# oscillators.net
KiCad netlist of a schematic drawn in EAGLE
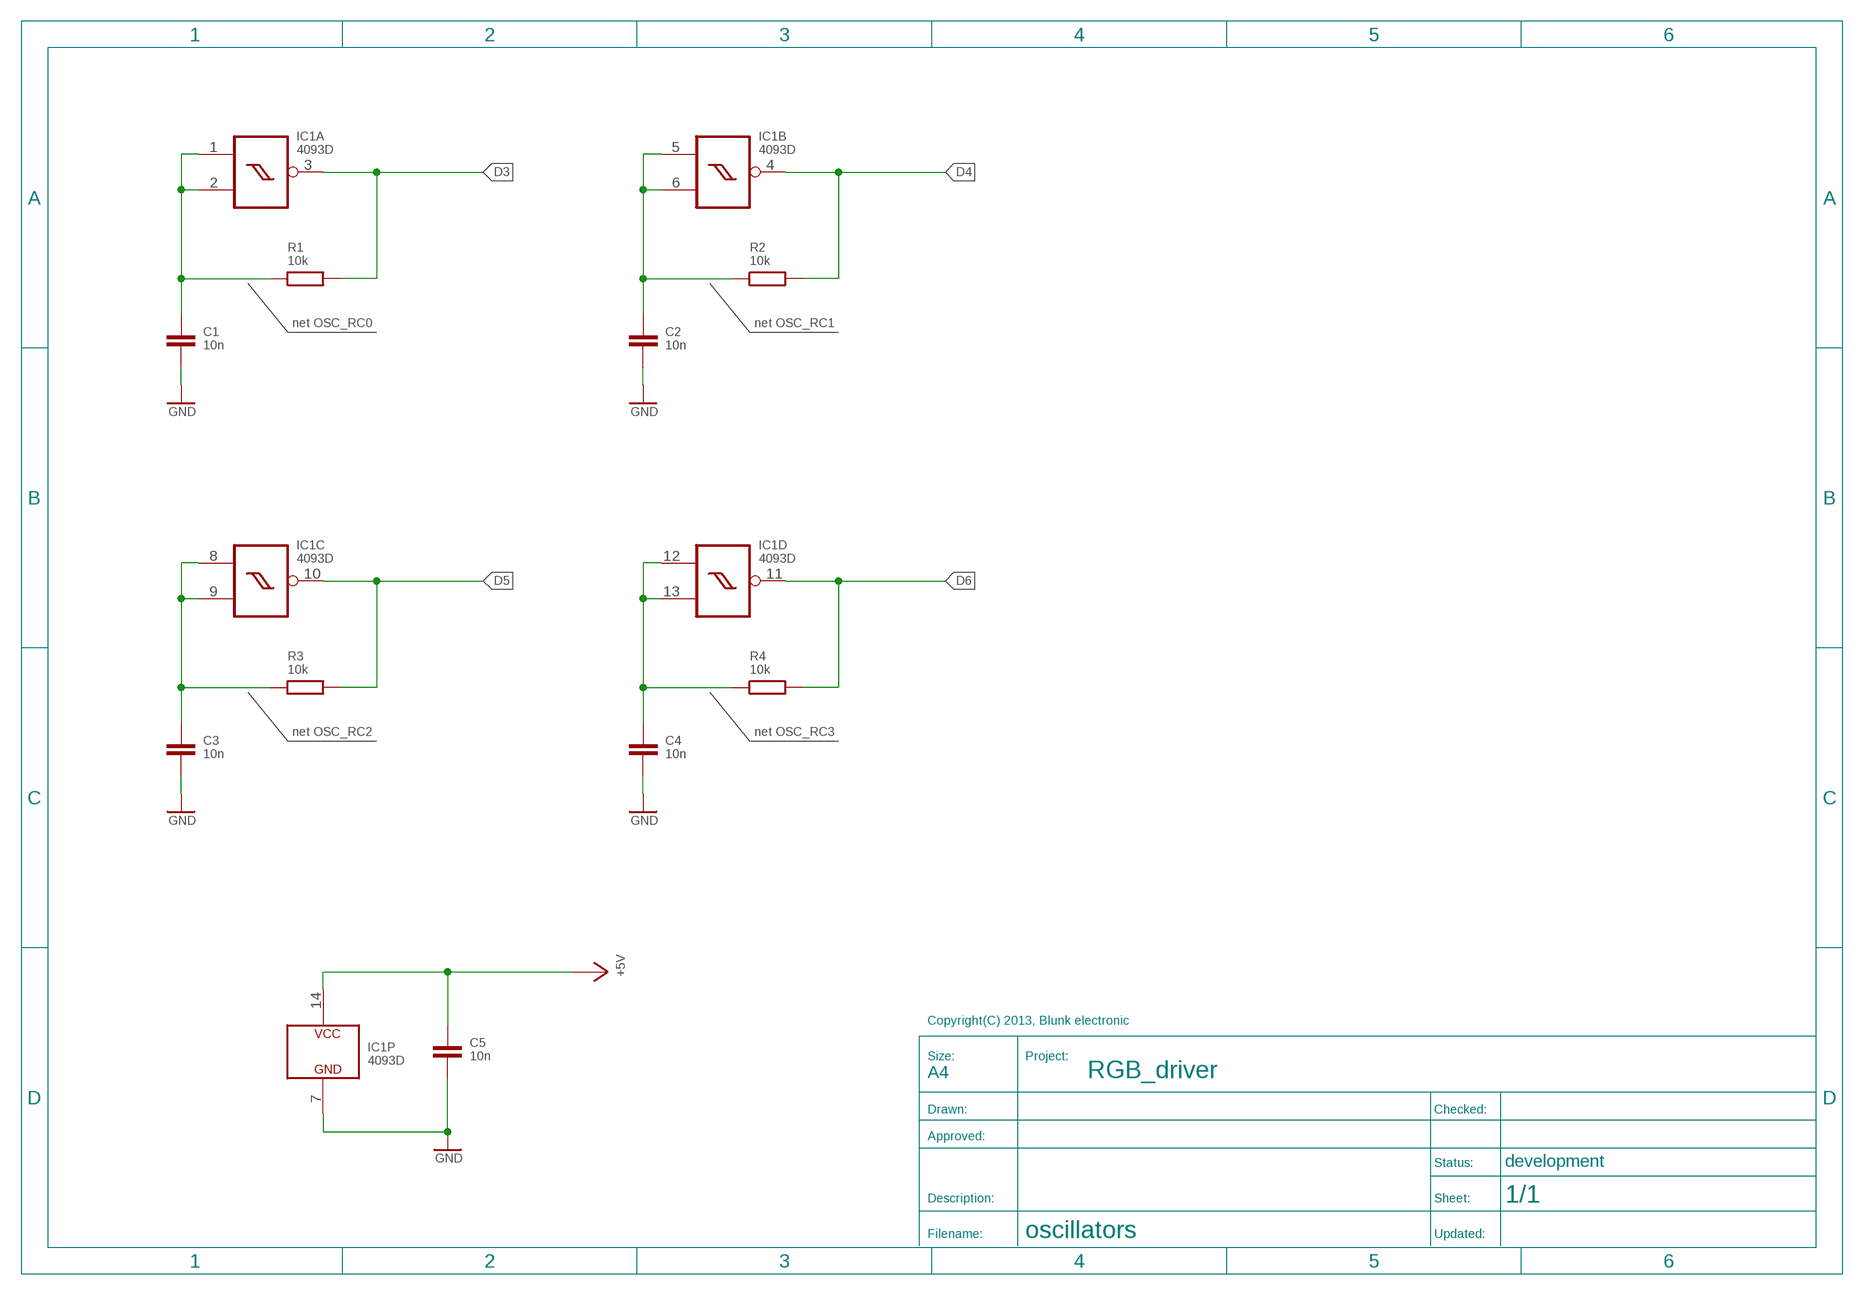
[diagram p0: schematic, sheet 1]

(export (version "E")
  (design (tool "Eeschema 10.0.6"))
  (components
    (comp (ref "C1")
      (value "10n")
      (footprint "eagle-import:S_0805")
      (libsource (lib "eagle-import") (part "C_EU_S_0805"))
    )
    (comp (ref "C2")
      (value "10n")
      (footprint "eagle-import:S_0805")
      (libsource (lib "eagle-import") (part "C_EU_S_0805"))
    )
    (comp (ref "C3")
      (value "10n")
      (footprint "eagle-import:S_0805")
      (libsource (lib "eagle-import") (part "C_EU_S_0805"))
    )
    (comp (ref "C4")
      (value "10n")
      (footprint "eagle-import:S_0805")
      (libsource (lib "eagle-import") (part "C_EU_S_0805"))
    )
    (comp (ref "C5")
      (value "10n")
      (footprint "eagle-import:S_0805")
      (libsource (lib "eagle-import") (part "C_EU_S_0805"))
    )
    (comp (ref "IC1")
      (value "4093D")
      (footprint "eagle-import:S_SO14")
      (libsource (lib "eagle-import") (part "4093D"))
    )
    (comp (ref "R1")
      (value "10k")
      (footprint "eagle-import:S_0805")
      (libsource (lib "eagle-import") (part "R_EU_S_0805"))
    )
    (comp (ref "R2")
      (value "10k")
      (footprint "eagle-import:S_0805")
      (libsource (lib "eagle-import") (part "R_EU_S_0805"))
    )
    (comp (ref "R3")
      (value "10k")
      (footprint "eagle-import:S_0805")
      (libsource (lib "eagle-import") (part "R_EU_S_0805"))
    )
    (comp (ref "R4")
      (value "10k")
      (footprint "eagle-import:S_0805")
      (libsource (lib "eagle-import") (part "R_EU_S_0805"))
    )
  )
  (nets
    (net (code "1") (name "+5V") (class "Default")
      (node (ref "C5") (pin "1") (pinfunction "1_1") (pintype "passive"))
      (node (ref "IC1") (pin "14") (pinfunction "VCC_14") (pintype "power_in"))
    )
    (net (code "2") (name "D3") (class "Default")
      (node (ref "IC1") (pin "3") (pinfunction "O_3") (pintype "output"))
      (node (ref "R1") (pin "2") (pinfunction "2_2") (pintype "passive"))
    )
    (net (code "3") (name "D4") (class "Default")
      (node (ref "IC1") (pin "4") (pinfunction "O_4") (pintype "output"))
      (node (ref "R2") (pin "2") (pinfunction "2_2") (pintype "passive"))
    )
    (net (code "4") (name "D5") (class "Default")
      (node (ref "IC1") (pin "10") (pinfunction "O_10") (pintype "output"))
      (node (ref "R3") (pin "2") (pinfunction "2_2") (pintype "passive"))
    )
    (net (code "5") (name "D6") (class "Default")
      (node (ref "IC1") (pin "11") (pinfunction "O_11") (pintype "output"))
      (node (ref "R4") (pin "2") (pinfunction "2_2") (pintype "passive"))
    )
    (net (code "6") (name "GND") (class "Default")
      (node (ref "C1") (pin "2") (pinfunction "2_2") (pintype "passive"))
      (node (ref "C2") (pin "2") (pinfunction "2_2") (pintype "passive"))
      (node (ref "C3") (pin "2") (pinfunction "2_2") (pintype "passive"))
      (node (ref "C4") (pin "2") (pinfunction "2_2") (pintype "passive"))
      (node (ref "C5") (pin "2") (pinfunction "2_2") (pintype "passive"))
      (node (ref "IC1") (pin "7") (pinfunction "GND_7") (pintype "power_in"))
    )
    (net (code "7") (name "Net-(IC1A-I0)") (class "Default")
      (node (ref "C1") (pin "1") (pinfunction "1_1") (pintype "passive"))
      (node (ref "IC1") (pin "1") (pinfunction "I0_1") (pintype "input"))
      (node (ref "IC1") (pin "2") (pinfunction "I1_2") (pintype "input"))
      (node (ref "R1") (pin "1") (pinfunction "1_1") (pintype "passive"))
    )
    (net (code "8") (name "Net-(IC1B-I0)") (class "Default")
      (node (ref "C2") (pin "1") (pinfunction "1_1") (pintype "passive"))
      (node (ref "IC1") (pin "5") (pinfunction "I0_5") (pintype "input"))
      (node (ref "IC1") (pin "6") (pinfunction "I1_6") (pintype "input"))
      (node (ref "R2") (pin "1") (pinfunction "1_1") (pintype "passive"))
    )
    (net (code "9") (name "Net-(IC1C-I0)") (class "Default")
      (node (ref "C3") (pin "1") (pinfunction "1_1") (pintype "passive"))
      (node (ref "IC1") (pin "8") (pinfunction "I0_8") (pintype "input"))
      (node (ref "IC1") (pin "9") (pinfunction "I1_9") (pintype "input"))
      (node (ref "R3") (pin "1") (pinfunction "1_1") (pintype "passive"))
    )
    (net (code "10") (name "Net-(IC1D-I0)") (class "Default")
      (node (ref "C4") (pin "1") (pinfunction "1_1") (pintype "passive"))
      (node (ref "IC1") (pin "12") (pinfunction "I0_12") (pintype "input"))
      (node (ref "IC1") (pin "13") (pinfunction "I1_13") (pintype "input"))
      (node (ref "R4") (pin "1") (pinfunction "1_1") (pintype "passive"))
    )
  )
)
